# spiceconverted.net
KiCad netlist of a schematic drawn in EAGLE
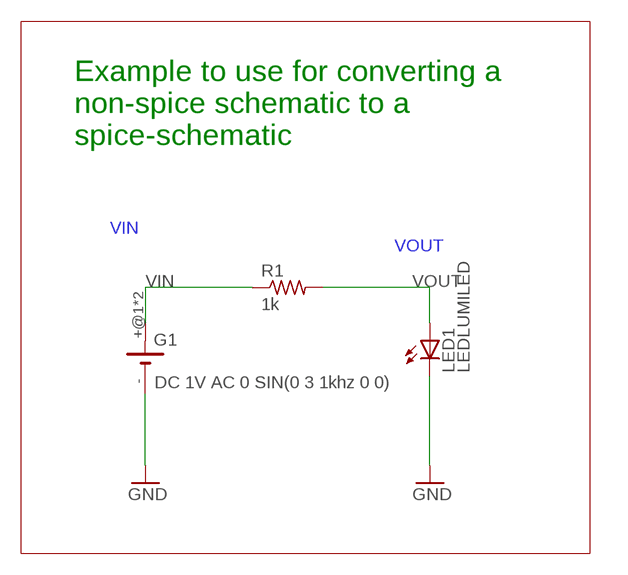
[diagram p0: schematic, sheet 1]

(export (version "E")
  (design (tool "Eeschema 10.0.6"))
  (components
    (comp (ref "G1")
      (value "DC 1V AC 0 SIN(0 3 1khz 0 0)")
      (footprint "eagle-import:10MM_SM_COIN_CELL_CLIP")
      (fields (field (name "SPICEPREFIX") "V"))
      (libsource (lib "eagle-import") (part "10MM_SM_COIN_CELL_CLIP"))
    )
    (comp (ref "LED1")
      (value "LEDLUMILED")
      (footprint "eagle-import:LUMILED")
      (fields (field (name "SPICEMODEL") "DMOD") (field (name "SPICEPREFIX") "D"))
      (libsource (lib "eagle-import") (part "LEDLUMILED"))
    )
    (comp (ref "R1")
      (value "1k")
      (footprint "eagle-import:0207_10")
      (fields (field (name "SPICEPREFIX") "R"))
      (libsource (lib "eagle-import") (part "R-US_0207/10"))
    )
  )
  (nets
    (net (code "1") (name "/VIN") (class "Default")
      (node (ref "G1") (pin "+@1") (pinfunction "+_+@1") (pintype "passive"))
      (node (ref "G1") (pin "+@2") (pinfunction "+_+@2") (pintype "passive"))
      (node (ref "R1") (pin "1") (pinfunction "1_1") (pintype "passive"))
    )
    (net (code "2") (name "/VOUT") (class "Default")
      (node (ref "LED1") (pin "2+") (pinfunction "A_2+") (pintype "passive"))
      (node (ref "R1") (pin "2") (pinfunction "2_2") (pintype "passive"))
    )
    (net (code "3") (name "GND") (class "Default")
      (node (ref "G1") (pin "-") (pinfunction "-_-") (pintype "passive"))
      (node (ref "LED1") (pin "4-") (pinfunction "C_4-") (pintype "passive"))
    )
  )
)
